# combo.net
KiCad netlist of a schematic drawn in EAGLE
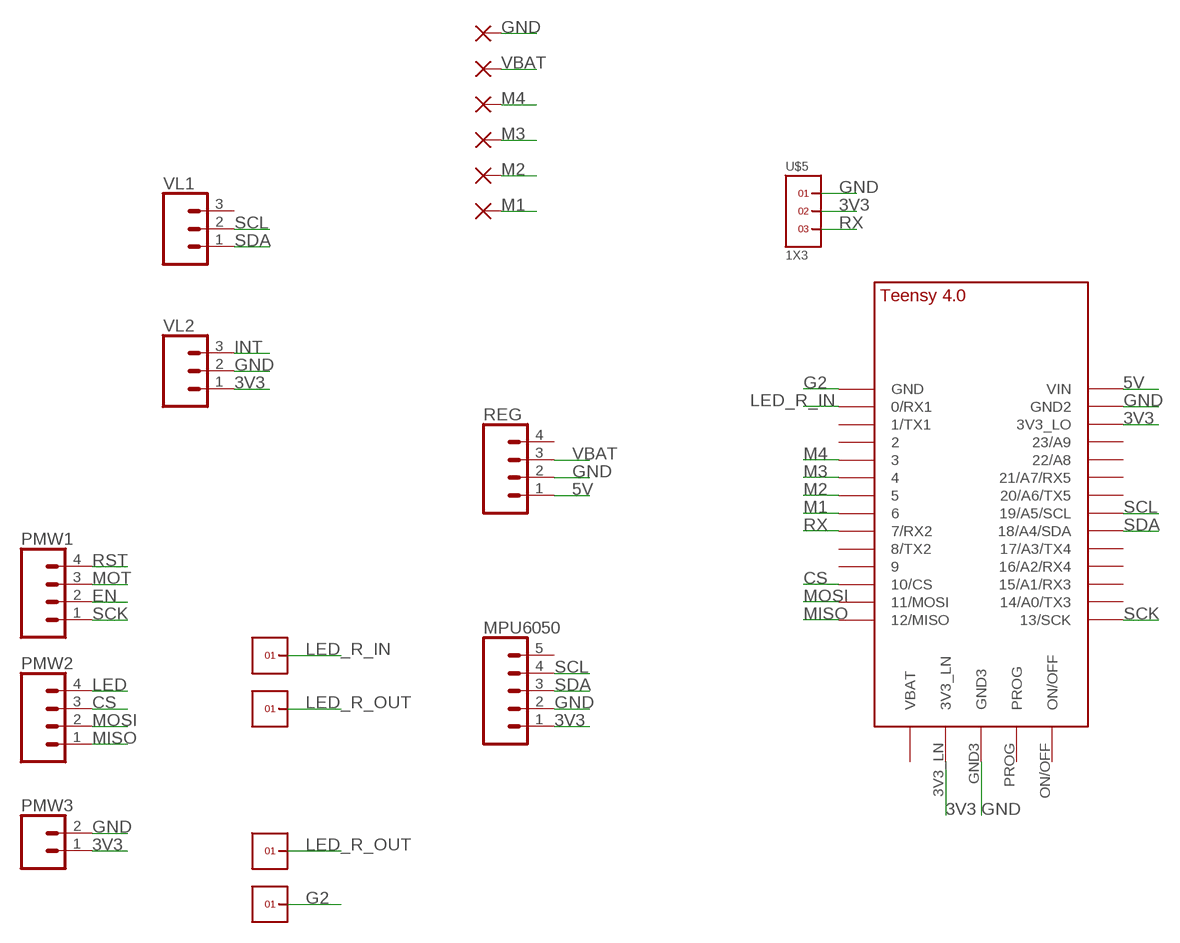
[diagram p0: schematic, sheet 1]

(export (version "E")
  (design (tool "Eeschema 10.0.6"))
  (components
    (comp (ref "GND")
      (value "SMD2")
      (footprint "eagle-import:SMD1,27-2,54")
      (libsource (lib "eagle-import") (part "SMD2"))
    )
    (comp (ref "M1")
      (value "SMD2")
      (footprint "eagle-import:SMD1,27-2,54")
      (libsource (lib "eagle-import") (part "SMD2"))
    )
    (comp (ref "M2")
      (value "SMD2")
      (footprint "eagle-import:SMD1,27-2,54")
      (libsource (lib "eagle-import") (part "SMD2"))
    )
    (comp (ref "M3")
      (value "SMD2")
      (footprint "eagle-import:SMD1,27-2,54")
      (libsource (lib "eagle-import") (part "SMD2"))
    )
    (comp (ref "M4")
      (value "SMD2")
      (footprint "eagle-import:SMD1,27-2,54")
      (libsource (lib "eagle-import") (part "SMD2"))
    )
    (comp (ref "MPU6050")
      (value "CONN_05NO_SILK")
      (footprint "eagle-import:1X05_NO_SILK")
      (libsource (lib "eagle-import") (part "CONN_05NO_SILK"))
    )
    (comp (ref "PMW1")
      (value "CONN_041X04_NO_SILK")
      (footprint "eagle-import:1X04_NO_SILK")
      (libsource (lib "eagle-import") (part "CONN_041X04_NO_SILK"))
    )
    (comp (ref "PMW2")
      (value "CONN_041X04_NO_SILK")
      (footprint "eagle-import:1X04_NO_SILK")
      (libsource (lib "eagle-import") (part "CONN_041X04_NO_SILK"))
    )
    (comp (ref "PMW3")
      (value "CONN_021X02_NO_SILK")
      (footprint "eagle-import:1X02_NO_SILK")
      (libsource (lib "eagle-import") (part "CONN_021X02_NO_SILK"))
    )
    (comp (ref "REG")
      (value "CONN_041X04_NO_SILK")
      (footprint "eagle-import:1X04_NO_SILK")
      (libsource (lib "eagle-import") (part "CONN_041X04_NO_SILK"))
    )
    (comp (ref "U$1")
      (value "TEENSY_4.0")
      (footprint "eagle-import:TEENSY_4.0")
      (libsource (lib "eagle-import") (part "TEENSY_4.0"))
    )
    (comp (ref "U$3")
      (value "1X1")
      (footprint "eagle-import:1X1")
      (libsource (lib "eagle-import") (part "1X1"))
    )
    (comp (ref "U$4")
      (value "1X1")
      (footprint "eagle-import:1X1")
      (libsource (lib "eagle-import") (part "1X1"))
    )
    (comp (ref "U$5")
      (value "1X3")
      (footprint "eagle-import:1X3")
      (libsource (lib "eagle-import") (part "1X3"))
    )
    (comp (ref "U$6")
      (value "1X1")
      (footprint "eagle-import:1X1")
      (libsource (lib "eagle-import") (part "1X1"))
    )
    (comp (ref "U$7")
      (value "1X1")
      (footprint "eagle-import:1X1")
      (libsource (lib "eagle-import") (part "1X1"))
    )
    (comp (ref "VBAT")
      (value "SMD2")
      (footprint "eagle-import:SMD1,27-2,54")
      (libsource (lib "eagle-import") (part "SMD2"))
    )
    (comp (ref "VL1")
      (value "CONN_031X03_NO_SILK")
      (footprint "eagle-import:1X03_NO_SILK")
      (libsource (lib "eagle-import") (part "CONN_031X03_NO_SILK"))
    )
    (comp (ref "VL2")
      (value "CONN_031X03_NO_SILK")
      (footprint "eagle-import:1X03_NO_SILK")
      (libsource (lib "eagle-import") (part "CONN_031X03_NO_SILK"))
    )
  )
  (nets
    (net (code "1") (name "/3V3") (class "Default")
      (node (ref "MPU6050") (pin "1") (pinfunction "1_1") (pintype "passive"))
      (node (ref "PMW3") (pin "1") (pinfunction "1_1") (pintype "passive"))
      (node (ref "U$1") (pin "3V3_LN") (pinfunction "3V3_LN_3V3_LN") (pintype "bidirectional"))
      (node (ref "U$1") (pin "3V3_LO") (pinfunction "3V3_LO_3V3_LO") (pintype "bidirectional"))
      (node (ref "U$5") (pin "2") (pinfunction "2_2") (pintype "bidirectional"))
      (node (ref "VL2") (pin "1") (pinfunction "1_1") (pintype "passive"))
    )
    (net (code "2") (name "/5V") (class "Default")
      (node (ref "REG") (pin "1") (pinfunction "1_1") (pintype "passive"))
      (node (ref "U$1") (pin "VIN") (pinfunction "VIN_VIN") (pintype "bidirectional"))
    )
    (net (code "3") (name "/CS") (class "Default")
      (node (ref "PMW2") (pin "3") (pinfunction "3_3") (pintype "passive"))
      (node (ref "U$1") (pin "10/CS") (pinfunction "10/CS_10/CS") (pintype "bidirectional"))
    )
    (net (code "4") (name "/EN") (class "Default")
      (node (ref "PMW1") (pin "2") (pinfunction "2_2") (pintype "passive"))
    )
    (net (code "5") (name "/G2") (class "Default")
      (node (ref "U$1") (pin "GND") (pinfunction "GND_GND") (pintype "bidirectional"))
      (node (ref "U$7") (pin "1") (pinfunction "1_1") (pintype "bidirectional"))
    )
    (net (code "6") (name "/GND") (class "Default")
      (node (ref "GND") (pin "1") (pinfunction "P_1") (pintype "passive"))
      (node (ref "MPU6050") (pin "2") (pinfunction "2_2") (pintype "passive"))
      (node (ref "PMW3") (pin "2") (pinfunction "2_2") (pintype "passive"))
      (node (ref "REG") (pin "2") (pinfunction "2_2") (pintype "passive"))
      (node (ref "U$1") (pin "GND2") (pinfunction "GND2_GND2") (pintype "bidirectional"))
      (node (ref "U$1") (pin "GND3") (pinfunction "GND3_GND3") (pintype "bidirectional"))
      (node (ref "U$5") (pin "1") (pinfunction "1_1") (pintype "bidirectional"))
      (node (ref "VL2") (pin "2") (pinfunction "2_2") (pintype "passive"))
    )
    (net (code "7") (name "/INT") (class "Default")
      (node (ref "VL2") (pin "3") (pinfunction "3_3") (pintype "passive"))
    )
    (net (code "8") (name "/LED") (class "Default")
      (node (ref "PMW2") (pin "4") (pinfunction "4_4") (pintype "passive"))
    )
    (net (code "9") (name "/LED_R_IN") (class "Default")
      (node (ref "U$1") (pin "0/RX") (pinfunction "0/RX1_0/RX") (pintype "bidirectional"))
      (node (ref "U$3") (pin "1") (pinfunction "1_1") (pintype "bidirectional"))
    )
    (net (code "10") (name "/LED_R_OUT") (class "Default")
      (node (ref "U$4") (pin "1") (pinfunction "1_1") (pintype "bidirectional"))
      (node (ref "U$6") (pin "1") (pinfunction "1_1") (pintype "bidirectional"))
    )
    (net (code "11") (name "/M1") (class "Default")
      (node (ref "M1") (pin "1") (pinfunction "P_1") (pintype "passive"))
      (node (ref "U$1") (pin "6") (pinfunction "6_6") (pintype "bidirectional"))
    )
    (net (code "12") (name "/M2") (class "Default")
      (node (ref "M2") (pin "1") (pinfunction "P_1") (pintype "passive"))
      (node (ref "U$1") (pin "5") (pinfunction "5_5") (pintype "bidirectional"))
    )
    (net (code "13") (name "/M3") (class "Default")
      (node (ref "M3") (pin "1") (pinfunction "P_1") (pintype "passive"))
      (node (ref "U$1") (pin "4/CANRX") (pinfunction "4_4/CANRX") (pintype "bidirectional"))
    )
    (net (code "14") (name "/M4") (class "Default")
      (node (ref "M4") (pin "1") (pinfunction "P_1") (pintype "passive"))
      (node (ref "U$1") (pin "3/CANTX") (pinfunction "3_3/CANTX") (pintype "bidirectional"))
    )
    (net (code "15") (name "/MISO") (class "Default")
      (node (ref "PMW2") (pin "1") (pinfunction "1_1") (pintype "passive"))
      (node (ref "U$1") (pin "12/MISO") (pinfunction "12/MISO_12/MISO") (pintype "bidirectional"))
    )
    (net (code "16") (name "/MOSI") (class "Default")
      (node (ref "PMW2") (pin "2") (pinfunction "2_2") (pintype "passive"))
      (node (ref "U$1") (pin "11/MOSI") (pinfunction "11/MOSI_11/MOSI") (pintype "bidirectional"))
    )
    (net (code "17") (name "/MOT") (class "Default")
      (node (ref "PMW1") (pin "3") (pinfunction "3_3") (pintype "passive"))
    )
    (net (code "18") (name "/RST") (class "Default")
      (node (ref "PMW1") (pin "4") (pinfunction "4_4") (pintype "passive"))
    )
    (net (code "19") (name "/RX") (class "Default")
      (node (ref "U$1") (pin "7") (pinfunction "7/RX2_7") (pintype "bidirectional"))
      (node (ref "U$5") (pin "3") (pinfunction "3_3") (pintype "bidirectional"))
    )
    (net (code "20") (name "/SCK") (class "Default")
      (node (ref "PMW1") (pin "1") (pinfunction "1_1") (pintype "passive"))
      (node (ref "U$1") (pin "13/SCK") (pinfunction "13/SCK_13/SCK") (pintype "bidirectional"))
    )
    (net (code "21") (name "/SCL") (class "Default")
      (node (ref "MPU6050") (pin "4") (pinfunction "4_4") (pintype "passive"))
      (node (ref "U$1") (pin "19/A5/SCL") (pinfunction "19/A5/SCL_19/A5/SCL") (pintype "bidirectional"))
      (node (ref "VL1") (pin "2") (pinfunction "2_2") (pintype "passive"))
    )
    (net (code "22") (name "/SDA") (class "Default")
      (node (ref "MPU6050") (pin "3") (pinfunction "3_3") (pintype "passive"))
      (node (ref "U$1") (pin "18/A4/SDA") (pinfunction "18/A4/SDA_18/A4/SDA") (pintype "bidirectional"))
      (node (ref "VL1") (pin "1") (pinfunction "1_1") (pintype "passive"))
    )
    (net (code "23") (name "/VBAT") (class "Default")
      (node (ref "REG") (pin "3") (pinfunction "3_3") (pintype "passive"))
      (node (ref "VBAT") (pin "1") (pinfunction "P_1") (pintype "passive"))
    )
    (net (code "24") (name "unconnected-(MPU6050-Pad5)") (class "Default")
      (node (ref "MPU6050") (pin "5") (pinfunction "5_5") (pintype "passive"))
    )
    (net (code "25") (name "unconnected-(REG-Pad4)") (class "Default")
      (node (ref "REG") (pin "4") (pinfunction "4_4") (pintype "passive"))
    )
    (net (code "26") (name "unconnected-(U$1-1{slash}TX1-Pad1{slash}TX)") (class "Default")
      (node (ref "U$1") (pin "1/TX") (pinfunction "1/TX1_1/TX") (pintype "bidirectional"))
    )
    (net (code "27") (name "unconnected-(U$1-8{slash}TX2-Pad8)") (class "Default")
      (node (ref "U$1") (pin "8") (pinfunction "8/TX2_8") (pintype "bidirectional"))
    )
    (net (code "28") (name "unconnected-(U$1-9-Pad9{slash}CS)") (class "Default")
      (node (ref "U$1") (pin "9/CS") (pinfunction "9_9/CS") (pintype "bidirectional"))
    )
    (net (code "29") (name "unconnected-(U$1-14{slash}A0{slash}TX3-Pad14{slash}A0)") (class "Default")
      (node (ref "U$1") (pin "14/A0") (pinfunction "14/A0/TX3_14/A0") (pintype "bidirectional"))
    )
    (net (code "30") (name "unconnected-(U$1-15{slash}A1{slash}RX3-Pad15{slash}A1)") (class "Default")
      (node (ref "U$1") (pin "15/A1") (pinfunction "15/A1/RX3_15/A1") (pintype "bidirectional"))
    )
    (net (code "31") (name "unconnected-(U$1-16{slash}A2{slash}RX4-Pad16{slash}A2)") (class "Default")
      (node (ref "U$1") (pin "16/A2") (pinfunction "16/A2/RX4_16/A2") (pintype "bidirectional"))
    )
    (net (code "32") (name "unconnected-(U$1-17{slash}A3{slash}TX4-Pad17{slash}A3)") (class "Default")
      (node (ref "U$1") (pin "17/A3") (pinfunction "17/A3/TX4_17/A3") (pintype "bidirectional"))
    )
    (net (code "33") (name "unconnected-(U$1-20{slash}A6{slash}TX5-Pad20{slash}A6)") (class "Default")
      (node (ref "U$1") (pin "20/A6") (pinfunction "20/A6/TX5_20/A6") (pintype "bidirectional"))
    )
    (net (code "34") (name "unconnected-(U$1-21{slash}A7{slash}RX5-Pad21{slash}A7)") (class "Default")
      (node (ref "U$1") (pin "21/A7") (pinfunction "21/A7/RX5_21/A7") (pintype "bidirectional"))
    )
    (net (code "35") (name "unconnected-(U$1-Pad2)") (class "Default")
      (node (ref "U$1") (pin "2") (pinfunction "2_2") (pintype "bidirectional"))
    )
    (net (code "36") (name "unconnected-(U$1-Pad22{slash}A8)") (class "Default")
      (node (ref "U$1") (pin "22/A8") (pinfunction "22/A8_22/A8") (pintype "bidirectional"))
    )
    (net (code "37") (name "unconnected-(U$1-Pad23{slash}A9)") (class "Default")
      (node (ref "U$1") (pin "23/A9") (pinfunction "23/A9_23/A9") (pintype "bidirectional"))
    )
    (net (code "38") (name "unconnected-(U$1-PadON{slash}OFF)") (class "Default")
      (node (ref "U$1") (pin "ON/OFF") (pinfunction "ON/OFF_ON/OFF") (pintype "bidirectional"))
    )
    (net (code "39") (name "unconnected-(U$1-PadPROG)") (class "Default")
      (node (ref "U$1") (pin "PROG") (pinfunction "PROG_PROG") (pintype "bidirectional"))
    )
    (net (code "40") (name "unconnected-(U$1-VBAT-PadVBAT\\)") (class "Default")
      (node (ref "U$1") (pin "VBAT\\") (pinfunction "VBAT_VBAT\\") (pintype "bidirectional"))
    )
    (net (code "41") (name "unconnected-(VL1-Pad3)") (class "Default")
      (node (ref "VL1") (pin "3") (pinfunction "3_3") (pintype "passive"))
    )
  )
)
